# blinkinch.net
KiCad netlist of a schematic drawn in EAGLE
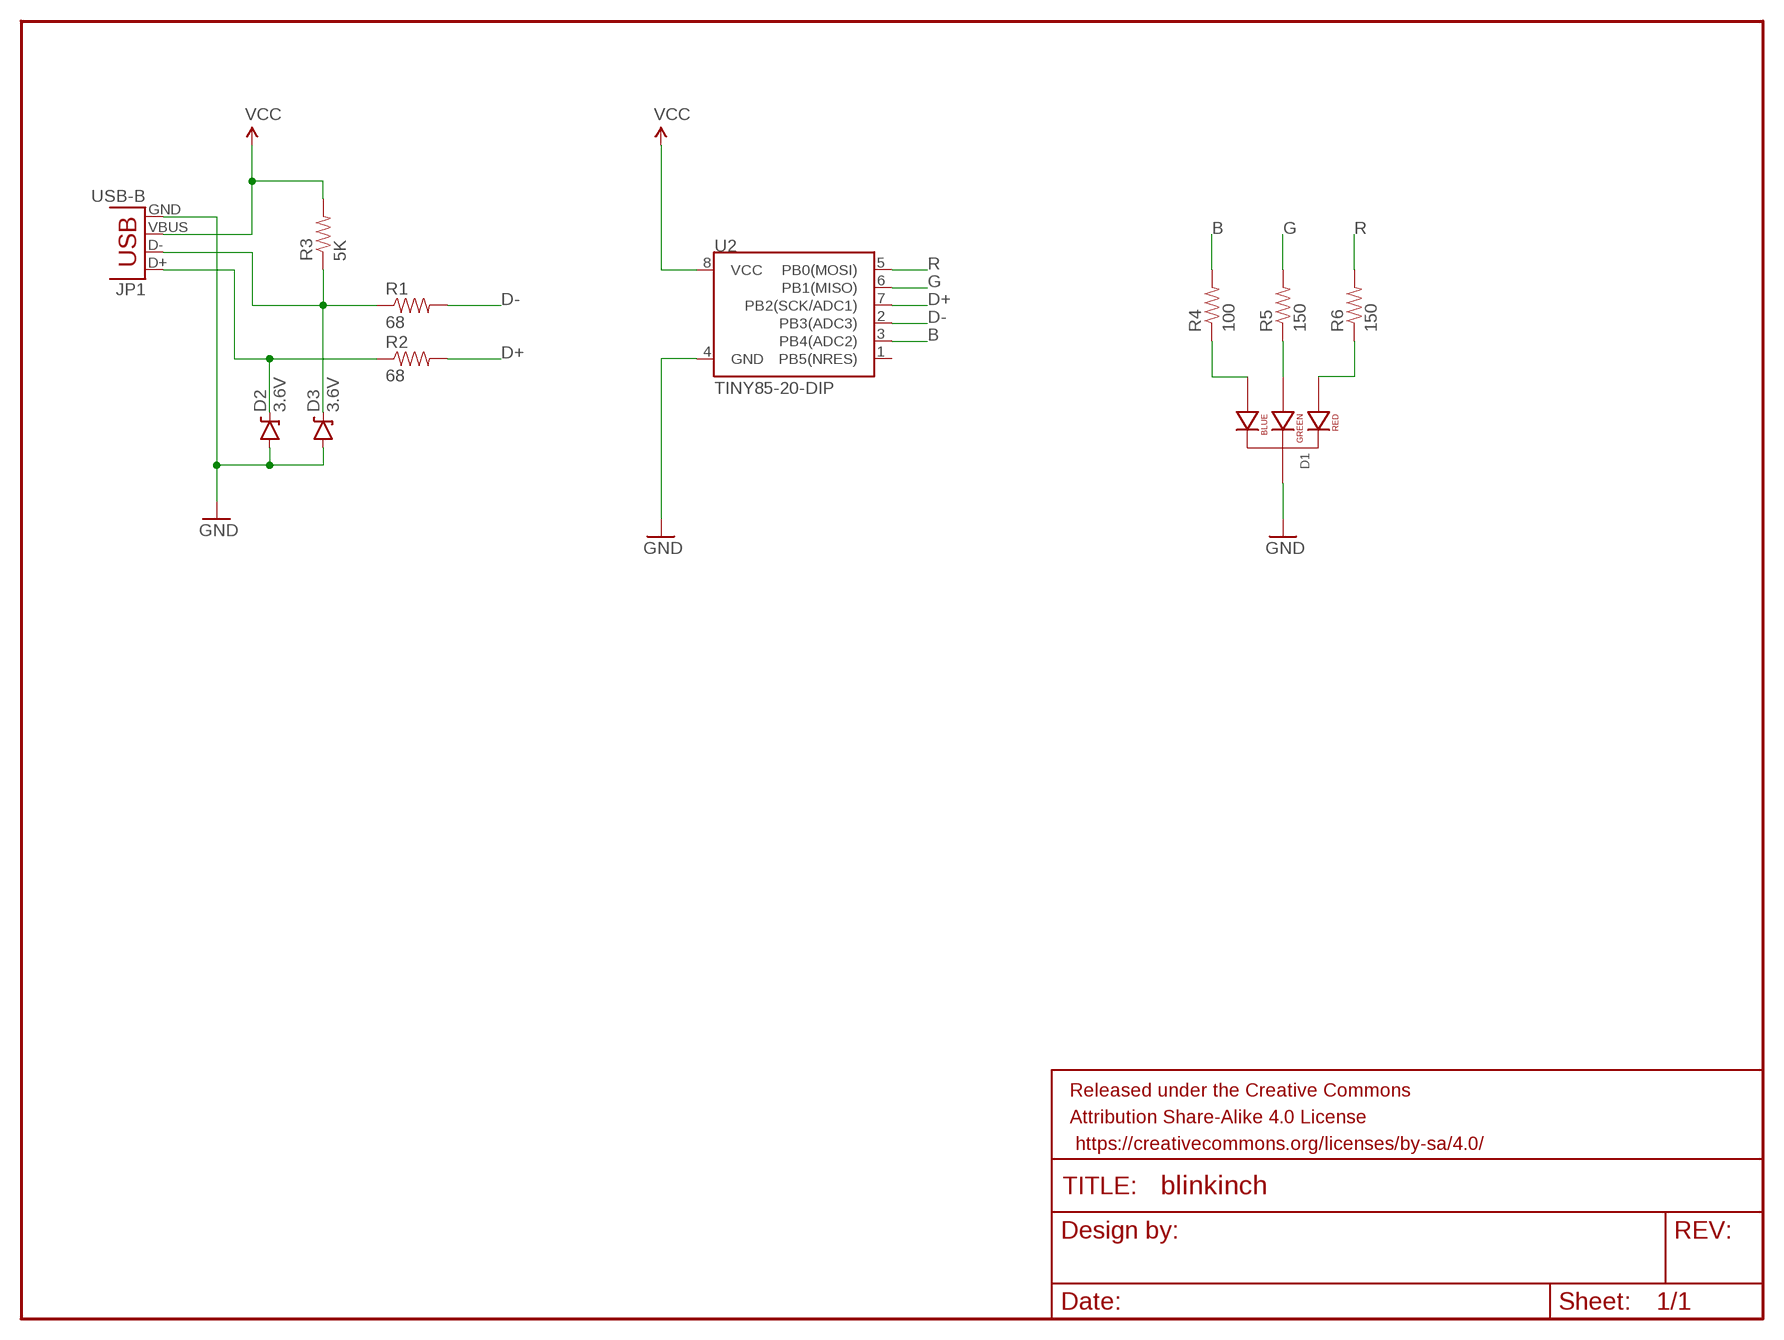
[diagram p0: schematic, sheet 1]

(export (version "E")
  (design (tool "Eeschema 10.0.6"))
  (components
    (comp (ref "D1")
      (value "LED-RGB-CC-THRUCLEAR")
      (footprint "eagle-import:LED-RGB-THRU")
      (libsource (lib "eagle-import") (part "LED-RGB-CC-THRUCLEAR"))
    )
    (comp (ref "D2")
      (value "3.6V")
      (footprint "eagle-import:DIODE-ZENER")
      (libsource (lib "eagle-import") (part "DIODE-ZENERPTH"))
    )
    (comp (ref "D3")
      (value "3.6V")
      (footprint "eagle-import:DIODE-ZENER")
      (libsource (lib "eagle-import") (part "DIODE-ZENERPTH"))
    )
    (comp (ref "FRAME1")
      (value "FRAME-LETTER")
      (footprint "eagle-import:CREATIVE_COMMONS")
      (libsource (lib "eagle-import") (part "FRAME-LETTER"))
    )
    (comp (ref "JP1")
      (value "USB-B")
      (footprint "eagle-import:USB-B-PTH")
      (libsource (lib "eagle-import") (part "USBPTH"))
    )
    (comp (ref "R1")
      (value "68")
      (footprint "eagle-import:AXIAL-0.1")
      (libsource (lib "eagle-import") (part "RESISTORPTH-1/4W-VERT"))
    )
    (comp (ref "R2")
      (value "68")
      (footprint "eagle-import:AXIAL-0.1")
      (libsource (lib "eagle-import") (part "RESISTORPTH-1/4W-VERT"))
    )
    (comp (ref "R3")
      (value "5K")
      (footprint "eagle-import:AXIAL-0.1")
      (libsource (lib "eagle-import") (part "RESISTORPTH-1/4W-VERT"))
    )
    (comp (ref "R4")
      (value "100")
      (footprint "eagle-import:AXIAL-0.1")
      (libsource (lib "eagle-import") (part "RESISTORPTH-1/4W-VERT"))
    )
    (comp (ref "R5")
      (value "150")
      (footprint "eagle-import:AXIAL-0.1")
      (libsource (lib "eagle-import") (part "RESISTORPTH-1/4W-VERT"))
    )
    (comp (ref "R6")
      (value "150")
      (footprint "eagle-import:AXIAL-0.1")
      (libsource (lib "eagle-import") (part "RESISTORPTH-1/4W-VERT"))
    )
    (comp (ref "U2")
      (value "TINY85-20-DIP")
      (footprint "eagle-import:DIP08")
      (libsource (lib "eagle-import") (part "ATTINY45TINY85-20-DIP"))
    )
  )
  (nets
    (net (code "1") (name "/B") (class "Default")
      (node (ref "R4") (pin "P$2") (pinfunction "2_P$2") (pintype "passive"))
      (node (ref "U2") (pin "3") (pinfunction "PB4(ADC2)_3") (pintype "bidirectional"))
    )
    (net (code "2") (name "/D+") (class "Default")
      (node (ref "R2") (pin "P$2") (pinfunction "2_P$2") (pintype "passive"))
      (node (ref "U2") (pin "7") (pinfunction "PB2(SCK/ADC1)_7") (pintype "bidirectional"))
    )
    (net (code "3") (name "/D-") (class "Default")
      (node (ref "R1") (pin "P$2") (pinfunction "2_P$2") (pintype "passive"))
      (node (ref "U2") (pin "2") (pinfunction "PB3(ADC3)_2") (pintype "bidirectional"))
    )
    (net (code "4") (name "/G") (class "Default")
      (node (ref "R5") (pin "P$2") (pinfunction "2_P$2") (pintype "passive"))
      (node (ref "U2") (pin "6") (pinfunction "PB1(MISO)_6") (pintype "bidirectional"))
    )
    (net (code "5") (name "/R") (class "Default")
      (node (ref "R6") (pin "P$2") (pinfunction "2_P$2") (pintype "passive"))
      (node (ref "U2") (pin "5") (pinfunction "PB0(MOSI)_5") (pintype "bidirectional"))
    )
    (net (code "6") (name "GND") (class "Default")
      (node (ref "D1") (pin "2") (pinfunction "CATHODE_2") (pintype "bidirectional"))
      (node (ref "D2") (pin "P$2") (pinfunction "A_P$2") (pintype "passive"))
      (node (ref "D3") (pin "P$2") (pinfunction "A_P$2") (pintype "passive"))
      (node (ref "JP1") (pin "GND") (pinfunction "GND_GND") (pintype "bidirectional"))
      (node (ref "U2") (pin "4") (pinfunction "GND_4") (pintype "bidirectional"))
    )
    (net (code "7") (name "Net-(D1-BLUE_CATHODE)") (class "Default")
      (node (ref "D1") (pin "4") (pinfunction "BLUE_CATHODE_4") (pintype "bidirectional"))
      (node (ref "R4") (pin "P$1") (pinfunction "1_P$1") (pintype "passive"))
    )
    (net (code "8") (name "Net-(D1-GREEN_CATHODE)") (class "Default")
      (node (ref "D1") (pin "3") (pinfunction "GREEN_CATHODE_3") (pintype "bidirectional"))
      (node (ref "R5") (pin "P$1") (pinfunction "1_P$1") (pintype "passive"))
    )
    (net (code "9") (name "Net-(D1-RED_CATHODE)") (class "Default")
      (node (ref "D1") (pin "1") (pinfunction "RED_CATHODE_1") (pintype "bidirectional"))
      (node (ref "R6") (pin "P$1") (pinfunction "1_P$1") (pintype "passive"))
    )
    (net (code "10") (name "Net-(D2-C)") (class "Default")
      (node (ref "D2") (pin "P$1") (pinfunction "C_P$1") (pintype "passive"))
      (node (ref "JP1") (pin "D+") (pinfunction "D+_D+") (pintype "bidirectional"))
      (node (ref "R2") (pin "P$1") (pinfunction "1_P$1") (pintype "passive"))
    )
    (net (code "11") (name "Net-(D3-C)") (class "Default")
      (node (ref "D3") (pin "P$1") (pinfunction "C_P$1") (pintype "passive"))
      (node (ref "JP1") (pin "D-") (pinfunction "D-_D-") (pintype "bidirectional"))
      (node (ref "R1") (pin "P$1") (pinfunction "1_P$1") (pintype "passive"))
      (node (ref "R3") (pin "P$1") (pinfunction "1_P$1") (pintype "passive"))
    )
    (net (code "12") (name "VCC") (class "Default")
      (node (ref "JP1") (pin "VBUS") (pinfunction "VBUS_VBUS") (pintype "bidirectional"))
      (node (ref "R3") (pin "P$2") (pinfunction "2_P$2") (pintype "passive"))
      (node (ref "U2") (pin "8") (pinfunction "VCC_8") (pintype "bidirectional"))
    )
    (net (code "13") (name "unconnected-(U2-PB5(NRES)-Pad1)") (class "Default")
      (node (ref "U2") (pin "1") (pinfunction "PB5(NRES)_1") (pintype "bidirectional"))
    )
  )
)
